# myRadioBreakout.net
KiCad netlist of a schematic drawn in EAGLE
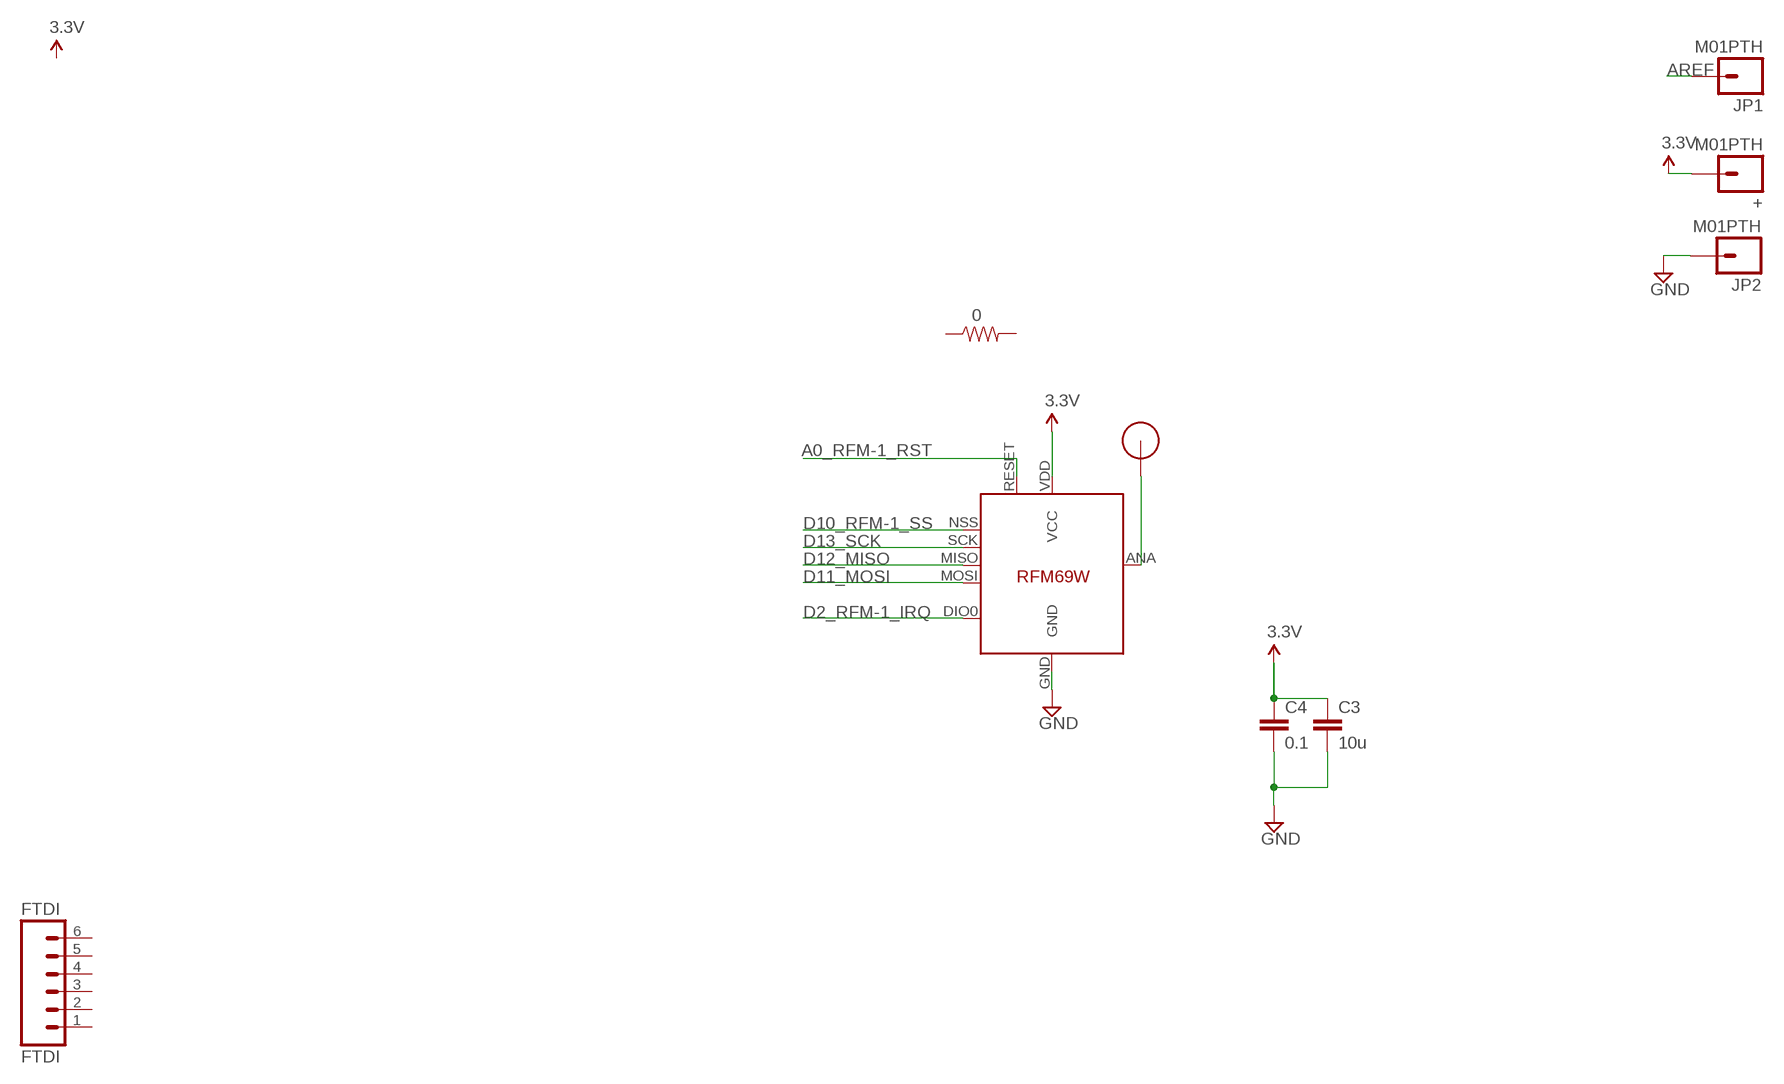
[diagram p0: schematic, sheet 1]

(export (version "E")
  (design (tool "Eeschema 10.0.6"))
  (components
    (comp (ref "+")
      (value "M01PTH")
      (footprint "eagle-import:1X01")
      (libsource (lib "eagle-import") (part "M01PTH"))
    )
    (comp (ref "C3")
      (value "10u")
      (footprint "eagle-import:0805-CAP")
      (libsource (lib "eagle-import") (part "CAP0805-CAP"))
    )
    (comp (ref "C4")
      (value "0.1")
      (footprint "eagle-import:0603-CAP")
      (libsource (lib "eagle-import") (part "CAP0603-CAP"))
    )
    (comp (ref "FTDI")
      (value "FTDI")
      (footprint "eagle-import:1X06")
      (libsource (lib "eagle-import") (part "M06SIP"))
    )
    (comp (ref "JP1")
      (value "M01PTH")
      (footprint "eagle-import:1X01")
      (libsource (lib "eagle-import") (part "M01PTH"))
    )
    (comp (ref "JP2")
      (value "M01PTH")
      (footprint "eagle-import:1X01")
      (libsource (lib "eagle-import") (part "M01PTH"))
    )
    (comp (ref "R1")
      (value "0")
      (footprint "eagle-import:0603-RES")
      (libsource (lib "eagle-import") (part "RESISTOR0603-RES"))
    )
    (comp (ref "U$1")
      (value "RFM12B_ANTENNA")
      (footprint "eagle-import:RFM12B-ANTENNA")
      (libsource (lib "eagle-import") (part "RFM12B_ANTENNA"))
    )
    (comp (ref "U$5")
      (value "RFM69_MINIPADS")
      (footprint "eagle-import:RFM69W-MINPADS")
      (libsource (lib "eagle-import") (part "RFM69_MINIPADS"))
    )
  )
  (nets
    (net (code "1") (name "/A0_RFM-1_RST") (class "Default")
      (node (ref "U$5") (pin "RESET") (pinfunction "RESET_RESET") (pintype "input"))
    )
    (net (code "2") (name "/AREF") (class "Default")
      (node (ref "JP1") (pin "1") (pinfunction "1_1") (pintype "passive"))
    )
    (net (code "3") (name "/D2_RFM-1_IRQ") (class "Default")
      (node (ref "U$5") (pin "DIO0") (pinfunction "DIO0/IRQ_DIO0") (pintype "open_collector"))
    )
    (net (code "4") (name "/D10_RFM-1_SS") (class "Default")
      (node (ref "U$5") (pin "NSS") (pinfunction "SEL_NSS") (pintype "input"))
    )
    (net (code "5") (name "/D11_MOSI") (class "Default")
      (node (ref "U$5") (pin "MOSI") (pinfunction "MOSI_MOSI") (pintype "output"))
    )
    (net (code "6") (name "/D12_MISO") (class "Default")
      (node (ref "U$5") (pin "MISO") (pinfunction "MISO_MISO") (pintype "input"))
    )
    (net (code "7") (name "/D13_SCK") (class "Default")
      (node (ref "U$5") (pin "SCK") (pinfunction "SCK_SCK") (pintype "input"))
    )
    (net (code "8") (name "3.3V") (class "Default")
      (node (ref "+") (pin "1") (pinfunction "1_1") (pintype "passive"))
      (node (ref "C3") (pin "1") (pinfunction "1_1") (pintype "passive"))
      (node (ref "C4") (pin "1") (pinfunction "1_1") (pintype "passive"))
      (node (ref "U$5") (pin "VDD") (pinfunction "VCC_VDD") (pintype "power_in"))
    )
    (net (code "9") (name "GND") (class "Default")
      (node (ref "C3") (pin "2") (pinfunction "2_2") (pintype "passive"))
      (node (ref "C4") (pin "2") (pinfunction "2_2") (pintype "passive"))
      (node (ref "JP2") (pin "1") (pinfunction "1_1") (pintype "passive"))
      (node (ref "U$5") (pin "GND") (pinfunction "GND_GND") (pintype "power_in"))
    )
    (net (code "10") (name "Net-(U$1-1)") (class "Default")
      (node (ref "U$1") (pin "P$1") (pinfunction "1_P$1") (pintype "bidirectional"))
      (node (ref "U$5") (pin "ANA") (pinfunction "ANT_ANA") (pintype "passive"))
    )
    (net (code "11") (name "unconnected-(FTDI-Pad1)") (class "Default")
      (node (ref "FTDI") (pin "1") (pinfunction "1_1") (pintype "passive"))
    )
    (net (code "12") (name "unconnected-(FTDI-Pad2)") (class "Default")
      (node (ref "FTDI") (pin "2") (pinfunction "2_2") (pintype "passive"))
    )
    (net (code "13") (name "unconnected-(FTDI-Pad3)") (class "Default")
      (node (ref "FTDI") (pin "3") (pinfunction "3_3") (pintype "passive"))
    )
    (net (code "14") (name "unconnected-(FTDI-Pad4)") (class "Default")
      (node (ref "FTDI") (pin "4") (pinfunction "4_4") (pintype "passive"))
    )
    (net (code "15") (name "unconnected-(FTDI-Pad5)") (class "Default")
      (node (ref "FTDI") (pin "5") (pinfunction "5_5") (pintype "passive"))
    )
    (net (code "16") (name "unconnected-(FTDI-Pad6)") (class "Default")
      (node (ref "FTDI") (pin "6") (pinfunction "6_6") (pintype "passive"))
    )
    (net (code "17") (name "unconnected-(R1-Pad1)") (class "Default")
      (node (ref "R1") (pin "1") (pinfunction "1_1") (pintype "passive"))
    )
    (net (code "18") (name "unconnected-(R1-Pad2)") (class "Default")
      (node (ref "R1") (pin "2") (pinfunction "2_2") (pintype "passive"))
    )
  )
)
